# ZIGBEE.net
KiCad netlist of a schematic drawn in Altium Designer
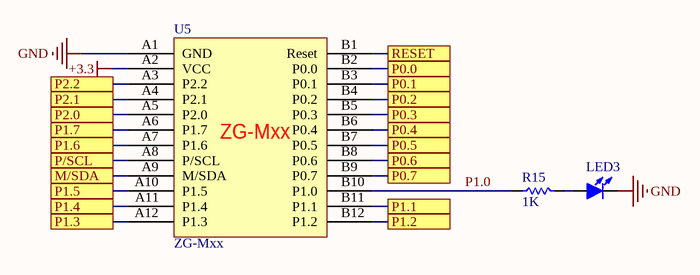
[diagram p0: ZIGBEE.SchDoc]

(export (version "E")
  (design (tool "Eeschema 10.0.6"))
  (components
    (comp (ref "LED3")
      (value "LED-SMD")
      (footprint "LED 0805B")
      (description "Patch LED")
      (fields (field (name "版权归属") "源创客"))
      (libsource (lib "LED") (part "LED-SMD"))
    )
    (comp (ref "R15")
      (value "1K")
      (footprint "R 0805")
      (description "Chip resistor")
      (fields (field (name "版权归属") "源创客"))
      (libsource (lib "Passive (Resistor-Capacitor-Inductor-Veristor-Ferrite)") (part "R"))
    )
    (comp (ref "U5")
      (value "ZG-Mxx")
      (footprint "ZG-M0/M1/M1E")
      (description "Zigbee Ghostyu")
      (libsource (lib "Module") (part "ZG-Mxx"))
    )
  )
  (nets
    (net (code "1") (name "+3.3") (class "Default")
      (node (ref "U5") (pin "A2") (pinfunction "VCC_A2") (pintype "passive"))
    )
    (net (code "2") (name "/M{slash}SDA") (class "Default")
      (node (ref "U5") (pin "A9") (pinfunction "M/SDA_A9") (pintype "passive"))
    )
    (net (code "3") (name "/P0.0") (class "Default")
      (node (ref "U5") (pin "B2") (pinfunction "P0.0_B2") (pintype "passive"))
    )
    (net (code "4") (name "/P0.1") (class "Default")
      (node (ref "U5") (pin "B3") (pinfunction "P0.1_B3") (pintype "passive"))
    )
    (net (code "5") (name "/P0.2") (class "Default")
      (node (ref "U5") (pin "B4") (pinfunction "P0.2_B4") (pintype "passive"))
    )
    (net (code "6") (name "/P0.3") (class "Default")
      (node (ref "U5") (pin "B5") (pinfunction "P0.3_B5") (pintype "passive"))
    )
    (net (code "7") (name "/P0.4") (class "Default")
      (node (ref "U5") (pin "B6") (pinfunction "P0.4_B6") (pintype "passive"))
    )
    (net (code "8") (name "/P0.5") (class "Default")
      (node (ref "U5") (pin "B7") (pinfunction "P0.5_B7") (pintype "passive"))
    )
    (net (code "9") (name "/P0.6") (class "Default")
      (node (ref "U5") (pin "B8") (pinfunction "P0.6_B8") (pintype "passive"))
    )
    (net (code "10") (name "/P0.7") (class "Default")
      (node (ref "U5") (pin "B9") (pinfunction "P0.7_B9") (pintype "passive"))
    )
    (net (code "11") (name "/P1.0") (class "Default")
      (node (ref "R15") (pin "1") (pinfunction "1_1") (pintype "passive"))
      (node (ref "U5") (pin "B10") (pinfunction "P1.0_B10") (pintype "passive"))
    )
    (net (code "12") (name "/P1.1") (class "Default")
      (node (ref "U5") (pin "B11") (pinfunction "P1.1_B11") (pintype "passive"))
    )
    (net (code "13") (name "/P1.2") (class "Default")
      (node (ref "U5") (pin "B12") (pinfunction "P1.2_B12") (pintype "passive"))
    )
    (net (code "14") (name "/P1.3") (class "Default")
      (node (ref "U5") (pin "A12") (pinfunction "P1.3_A12") (pintype "passive"))
    )
    (net (code "15") (name "/P1.4") (class "Default")
      (node (ref "U5") (pin "A11") (pinfunction "P1.4_A11") (pintype "passive"))
    )
    (net (code "16") (name "/P1.5") (class "Default")
      (node (ref "U5") (pin "A10") (pinfunction "P1.5_A10") (pintype "passive"))
    )
    (net (code "17") (name "/P1.6") (class "Default")
      (node (ref "U5") (pin "A7") (pinfunction "P1.6_A7") (pintype "passive"))
    )
    (net (code "18") (name "/P1.7") (class "Default")
      (node (ref "U5") (pin "A6") (pinfunction "P1.7_A6") (pintype "passive"))
    )
    (net (code "19") (name "/P2.0") (class "Default")
      (node (ref "U5") (pin "A5") (pinfunction "P2.0_A5") (pintype "passive"))
    )
    (net (code "20") (name "/P2.1") (class "Default")
      (node (ref "U5") (pin "A4") (pinfunction "P2.1_A4") (pintype "passive"))
    )
    (net (code "21") (name "/P2.2") (class "Default")
      (node (ref "U5") (pin "A3") (pinfunction "P2.2_A3") (pintype "passive"))
    )
    (net (code "22") (name "/P{slash}SCL") (class "Default")
      (node (ref "U5") (pin "A8") (pinfunction "P/SCL_A8") (pintype "passive"))
    )
    (net (code "23") (name "/RESET") (class "Default")
      (node (ref "U5") (pin "B1") (pinfunction "Reset_B1") (pintype "passive"))
    )
    (net (code "24") (name "GND") (class "Default")
      (node (ref "LED3") (pin "2") (pinfunction "K_2") (pintype "passive"))
      (node (ref "U5") (pin "A1") (pinfunction "GND_A1") (pintype "passive"))
    )
    (net (code "25") (name "Net-(LED3-A)") (class "Default")
      (node (ref "LED3") (pin "1") (pinfunction "A_1") (pintype "passive"))
      (node (ref "R15") (pin "2") (pinfunction "2_2") (pintype "passive"))
    )
  )
)
